# sparrow-smd-jack.net
KiCad netlist of a schematic drawn in EAGLE
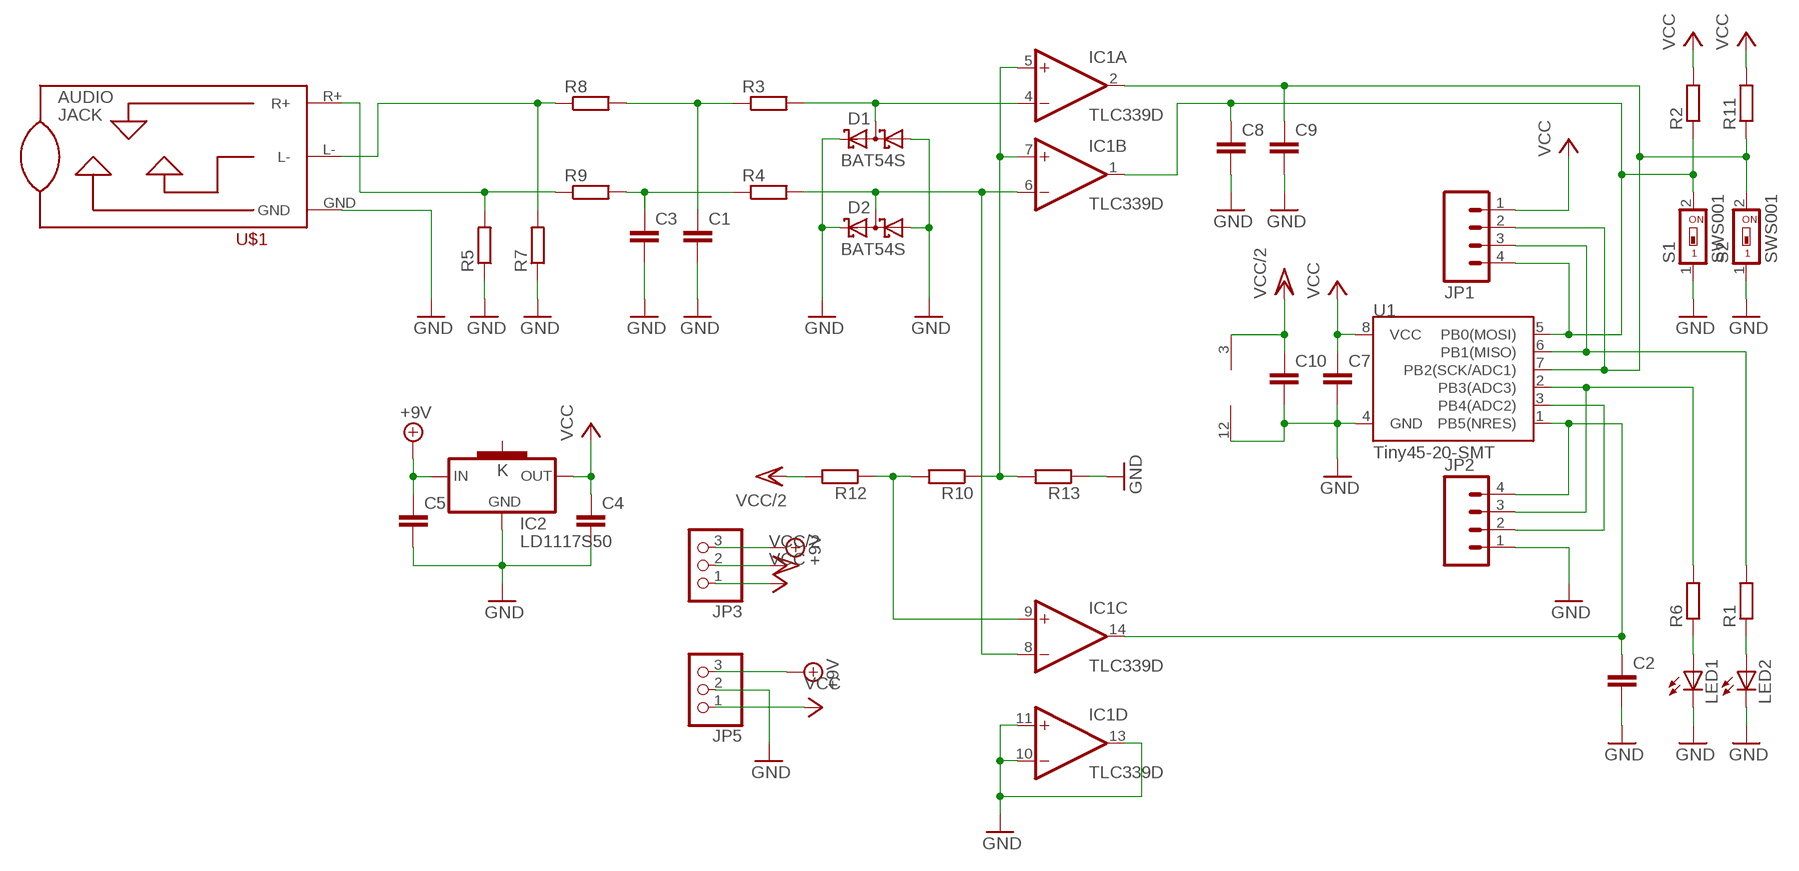
[diagram p0: schematic, sheet 1]

(export (version "E")
  (design (tool "Eeschema 10.0.6"))
  (components
    (comp (ref "C1")
      (value "C-EUC0805K")
      (footprint "eagle-import:C0805K")
      (libsource (lib "eagle-import") (part "C-EUC0805K"))
    )
    (comp (ref "C2")
      (value "C-EUC0805K")
      (footprint "eagle-import:C0805K")
      (libsource (lib "eagle-import") (part "C-EUC0805K"))
    )
    (comp (ref "C3")
      (value "C-EUC0805K")
      (footprint "eagle-import:C0805K")
      (libsource (lib "eagle-import") (part "C-EUC0805K"))
    )
    (comp (ref "C4")
      (value "C-EUC0805K")
      (footprint "eagle-import:C0805K")
      (libsource (lib "eagle-import") (part "C-EUC0805K"))
    )
    (comp (ref "C5")
      (value "C-EUC0805K")
      (footprint "eagle-import:C0805K")
      (libsource (lib "eagle-import") (part "C-EUC0805K"))
    )
    (comp (ref "C7")
      (value "C-EUC0805K")
      (footprint "eagle-import:C0805K")
      (libsource (lib "eagle-import") (part "C-EUC0805K"))
    )
    (comp (ref "C8")
      (value "C-EUC0805K")
      (footprint "eagle-import:C0805K")
      (libsource (lib "eagle-import") (part "C-EUC0805K"))
    )
    (comp (ref "C9")
      (value "C-EUC0805K")
      (footprint "eagle-import:C0805K")
      (libsource (lib "eagle-import") (part "C-EUC0805K"))
    )
    (comp (ref "C10")
      (value "C-EUC0805K")
      (footprint "eagle-import:C0805K")
      (libsource (lib "eagle-import") (part "C-EUC0805K"))
    )
    (comp (ref "D1")
      (value "BAT54S")
      (footprint "eagle-import:SOT23")
      (libsource (lib "eagle-import") (part "BAT54S"))
    )
    (comp (ref "D2")
      (value "BAT54S")
      (footprint "eagle-import:SOT23")
      (libsource (lib "eagle-import") (part "BAT54S"))
    )
    (comp (ref "IC1")
      (value "TLC339D")
      (footprint "eagle-import:SO14")
      (libsource (lib "eagle-import") (part "TLC339D"))
    )
    (comp (ref "IC2")
      (value "LD1117S50")
      (footprint "eagle-import:SOT223")
      (libsource (lib "eagle-import") (part "LD1117S50"))
    )
    (comp (ref "JP1")
      (value "M04PTH")
      (footprint "eagle-import:1X04")
      (libsource (lib "eagle-import") (part "M04PTH"))
    )
    (comp (ref "JP2")
      (value "M04PTH")
      (footprint "eagle-import:1X04")
      (libsource (lib "eagle-import") (part "M04PTH"))
    )
    (comp (ref "JP3")
      (value "PINHD-1X3")
      (footprint "eagle-import:1X03")
      (libsource (lib "eagle-import") (part "PINHD-1X3"))
    )
    (comp (ref "JP5")
      (value "PINHD-1X3")
      (footprint "eagle-import:1X03")
      (libsource (lib "eagle-import") (part "PINHD-1X3"))
    )
    (comp (ref "LED1")
      (value "LEDCHIP-LED0805")
      (footprint "eagle-import:CHIP-LED0805")
      (libsource (lib "eagle-import") (part "LEDCHIP-LED0805"))
    )
    (comp (ref "LED2")
      (value "LEDCHIP-LED0805")
      (footprint "eagle-import:CHIP-LED0805")
      (libsource (lib "eagle-import") (part "LEDCHIP-LED0805"))
    )
    (comp (ref "R1")
      (value "R-EU_M0805")
      (footprint "eagle-import:M0805")
      (libsource (lib "eagle-import") (part "R-EU_M0805"))
    )
    (comp (ref "R2")
      (value "R-EU_M0805")
      (footprint "eagle-import:M0805")
      (libsource (lib "eagle-import") (part "R-EU_M0805"))
    )
    (comp (ref "R3")
      (value "R-EU_M0805")
      (footprint "eagle-import:M0805")
      (libsource (lib "eagle-import") (part "R-EU_M0805"))
    )
    (comp (ref "R4")
      (value "R-EU_M0805")
      (footprint "eagle-import:M0805")
      (libsource (lib "eagle-import") (part "R-EU_M0805"))
    )
    (comp (ref "R5")
      (value "R-EU_M0805")
      (footprint "eagle-import:M0805")
      (libsource (lib "eagle-import") (part "R-EU_M0805"))
    )
    (comp (ref "R6")
      (value "R-EU_M0805")
      (footprint "eagle-import:M0805")
      (libsource (lib "eagle-import") (part "R-EU_M0805"))
    )
    (comp (ref "R7")
      (value "R-EU_M0805")
      (footprint "eagle-import:M0805")
      (libsource (lib "eagle-import") (part "R-EU_M0805"))
    )
    (comp (ref "R8")
      (value "R-EU_M0805")
      (footprint "eagle-import:M0805")
      (libsource (lib "eagle-import") (part "R-EU_M0805"))
    )
    (comp (ref "R9")
      (value "R-EU_M0805")
      (footprint "eagle-import:M0805")
      (libsource (lib "eagle-import") (part "R-EU_M0805"))
    )
    (comp (ref "R10")
      (value "R-EU_M0805")
      (footprint "eagle-import:M0805")
      (libsource (lib "eagle-import") (part "R-EU_M0805"))
    )
    (comp (ref "R11")
      (value "R-EU_M0805")
      (footprint "eagle-import:M0805")
      (libsource (lib "eagle-import") (part "R-EU_M0805"))
    )
    (comp (ref "R12")
      (value "R-EU_M0805")
      (footprint "eagle-import:M0805")
      (libsource (lib "eagle-import") (part "R-EU_M0805"))
    )
    (comp (ref "R13")
      (value "R-EU_M0805")
      (footprint "eagle-import:M0805")
      (libsource (lib "eagle-import") (part "R-EU_M0805"))
    )
    (comp (ref "S1")
      (value "SWS001")
      (footprint "eagle-import:SMS-001")
      (libsource (lib "eagle-import") (part "SWS001"))
    )
    (comp (ref "S2")
      (value "SWS001")
      (footprint "eagle-import:SMS-001")
      (libsource (lib "eagle-import") (part "SWS001"))
    )
    (comp (ref "U$1")
      (value "AUDIO-JACK-SMDSMD")
      (footprint "eagle-import:AUDIO-JACK-SMD")
      (libsource (lib "eagle-import") (part "AUDIO-JACK-SMDSMD"))
    )
    (comp (ref "U1")
      (value "Tiny45-20-SMT")
      (footprint "eagle-import:SO08-EIAJ")
      (libsource (lib "eagle-import") (part "ATTINY45TINY45-20-SMT"))
    )
  )
  (nets
    (net (code "1") (name "+9V") (class "Default")
      (node (ref "C5") (pin "1") (pinfunction "1_1") (pintype "passive"))
      (node (ref "IC2") (pin "3") (pinfunction "IN_3") (pintype "input"))
      (node (ref "JP3") (pin "3") (pinfunction "3_3") (pintype "passive"))
      (node (ref "JP5") (pin "3") (pinfunction "3_3") (pintype "passive"))
    )
    (net (code "2") (name "GND") (class "Default")
      (node (ref "C1") (pin "2") (pinfunction "2_2") (pintype "passive"))
      (node (ref "C10") (pin "2") (pinfunction "2_2") (pintype "passive"))
      (node (ref "C2") (pin "2") (pinfunction "2_2") (pintype "passive"))
      (node (ref "C3") (pin "2") (pinfunction "2_2") (pintype "passive"))
      (node (ref "C4") (pin "2") (pinfunction "2_2") (pintype "passive"))
      (node (ref "C5") (pin "2") (pinfunction "2_2") (pintype "passive"))
      (node (ref "C7") (pin "2") (pinfunction "2_2") (pintype "passive"))
      (node (ref "C8") (pin "2") (pinfunction "2_2") (pintype "passive"))
      (node (ref "C9") (pin "2") (pinfunction "2_2") (pintype "passive"))
      (node (ref "D1") (pin "1") (pinfunction "A1_1") (pintype "passive"))
      (node (ref "D1") (pin "2") (pinfunction "C2_2") (pintype "passive"))
      (node (ref "D2") (pin "1") (pinfunction "A1_1") (pintype "passive"))
      (node (ref "D2") (pin "2") (pinfunction "C2_2") (pintype "passive"))
      (node (ref "IC1") (pin "10") (pinfunction "-IN_10") (pintype "input"))
      (node (ref "IC1") (pin "11") (pinfunction "+IN_11") (pintype "input"))
      (node (ref "IC1") (pin "12") (pinfunction "V-_12") (pintype "power_in"))
      (node (ref "IC1") (pin "13") (pinfunction "OUT_13") (pintype "output"))
      (node (ref "IC2") (pin "1") (pinfunction "GND_1") (pintype "input"))
      (node (ref "JP2") (pin "1") (pinfunction "1_1") (pintype "passive"))
      (node (ref "JP5") (pin "2") (pinfunction "2_2") (pintype "passive"))
      (node (ref "LED1") (pin "C") (pinfunction "C_C") (pintype "passive"))
      (node (ref "LED2") (pin "C") (pinfunction "C_C") (pintype "passive"))
      (node (ref "R13") (pin "1") (pinfunction "1_1") (pintype "passive"))
      (node (ref "R5") (pin "1") (pinfunction "1_1") (pintype "passive"))
      (node (ref "R7") (pin "1") (pinfunction "1_1") (pintype "passive"))
      (node (ref "S1") (pin "1") (pinfunction "1_1") (pintype "passive"))
      (node (ref "S2") (pin "1") (pinfunction "1_1") (pintype "passive"))
      (node (ref "U$1") (pin "GND") (pinfunction "GND_GND") (pintype "bidirectional"))
      (node (ref "U1") (pin "4") (pinfunction "GND_4") (pintype "bidirectional"))
    )
    (net (code "3") (name "Net-(C1-Pad1)") (class "Default")
      (node (ref "C1") (pin "1") (pinfunction "1_1") (pintype "passive"))
      (node (ref "R3") (pin "1") (pinfunction "1_1") (pintype "passive"))
      (node (ref "R8") (pin "2") (pinfunction "2_2") (pintype "passive"))
    )
    (net (code "4") (name "Net-(C3-Pad1)") (class "Default")
      (node (ref "C3") (pin "1") (pinfunction "1_1") (pintype "passive"))
      (node (ref "R4") (pin "1") (pinfunction "1_1") (pintype "passive"))
      (node (ref "R9") (pin "2") (pinfunction "2_2") (pintype "passive"))
    )
    (net (code "5") (name "Net-(D1-C1A2)") (class "Default")
      (node (ref "D1") (pin "3") (pinfunction "C1A2_3") (pintype "passive"))
      (node (ref "IC1") (pin "4") (pinfunction "-IN_4") (pintype "input"))
      (node (ref "R3") (pin "2") (pinfunction "2_2") (pintype "passive"))
    )
    (net (code "6") (name "Net-(D2-C1A2)") (class "Default")
      (node (ref "D2") (pin "3") (pinfunction "C1A2_3") (pintype "passive"))
      (node (ref "IC1") (pin "6") (pinfunction "-IN_6") (pintype "input"))
      (node (ref "IC1") (pin "8") (pinfunction "-IN_8") (pintype "input"))
      (node (ref "R4") (pin "2") (pinfunction "2_2") (pintype "passive"))
    )
    (net (code "7") (name "Net-(IC1A-+IN)") (class "Default")
      (node (ref "IC1") (pin "5") (pinfunction "+IN_5") (pintype "input"))
      (node (ref "IC1") (pin "7") (pinfunction "+IN_7") (pintype "input"))
      (node (ref "R10") (pin "1") (pinfunction "1_1") (pintype "passive"))
      (node (ref "R13") (pin "2") (pinfunction "2_2") (pintype "passive"))
    )
    (net (code "8") (name "Net-(IC1A-OUT)") (class "Default")
      (node (ref "C9") (pin "1") (pinfunction "1_1") (pintype "passive"))
      (node (ref "IC1") (pin "2") (pinfunction "OUT_2") (pintype "output"))
      (node (ref "JP1") (pin "2") (pinfunction "2_2") (pintype "passive"))
      (node (ref "R11") (pin "1") (pinfunction "1_1") (pintype "passive"))
      (node (ref "S2") (pin "2") (pinfunction "2_2") (pintype "passive"))
      (node (ref "U1") (pin "7") (pinfunction "PB2(SCK/ADC1)_7") (pintype "bidirectional"))
    )
    (net (code "9") (name "Net-(IC1B-OUT)") (class "Default")
      (node (ref "C8") (pin "1") (pinfunction "1_1") (pintype "passive"))
      (node (ref "IC1") (pin "1") (pinfunction "OUT_1") (pintype "output"))
      (node (ref "JP1") (pin "4") (pinfunction "4_4") (pintype "passive"))
      (node (ref "R2") (pin "1") (pinfunction "1_1") (pintype "passive"))
      (node (ref "S1") (pin "2") (pinfunction "2_2") (pintype "passive"))
      (node (ref "U1") (pin "5") (pinfunction "PB0(MOSI)_5") (pintype "bidirectional"))
    )
    (net (code "10") (name "Net-(IC1C-+IN)") (class "Default")
      (node (ref "IC1") (pin "9") (pinfunction "+IN_9") (pintype "input"))
      (node (ref "R10") (pin "2") (pinfunction "2_2") (pintype "passive"))
      (node (ref "R12") (pin "1") (pinfunction "1_1") (pintype "passive"))
    )
    (net (code "11") (name "Net-(IC1C-OUT)") (class "Default")
      (node (ref "C2") (pin "1") (pinfunction "1_1") (pintype "passive"))
      (node (ref "IC1") (pin "14") (pinfunction "OUT_14") (pintype "output"))
      (node (ref "JP2") (pin "4") (pinfunction "4_4") (pintype "passive"))
      (node (ref "U1") (pin "1") (pinfunction "PB5(NRES)_1") (pintype "bidirectional"))
    )
    (net (code "12") (name "Net-(LED1-PadA)") (class "Default")
      (node (ref "LED1") (pin "A") (pinfunction "A_A") (pintype "passive"))
      (node (ref "R6") (pin "1") (pinfunction "1_1") (pintype "passive"))
    )
    (net (code "13") (name "Net-(LED2-PadA)") (class "Default")
      (node (ref "LED2") (pin "A") (pinfunction "A_A") (pintype "passive"))
      (node (ref "R1") (pin "1") (pinfunction "1_1") (pintype "passive"))
    )
    (net (code "14") (name "Net-(R5-Pad2)") (class "Default")
      (node (ref "R5") (pin "2") (pinfunction "2_2") (pintype "passive"))
      (node (ref "R9") (pin "1") (pinfunction "1_1") (pintype "passive"))
      (node (ref "U$1") (pin "R+") (pinfunction "R+_R+") (pintype "bidirectional"))
    )
    (net (code "15") (name "Net-(R7-Pad2)") (class "Default")
      (node (ref "R7") (pin "2") (pinfunction "2_2") (pintype "passive"))
      (node (ref "R8") (pin "1") (pinfunction "1_1") (pintype "passive"))
      (node (ref "U$1") (pin "L-") (pinfunction "L-_L-") (pintype "bidirectional"))
    )
    (net (code "16") (name "Net-(U1-PB1(MISO))") (class "Default")
      (node (ref "JP1") (pin "3") (pinfunction "3_3") (pintype "passive"))
      (node (ref "R1") (pin "2") (pinfunction "2_2") (pintype "passive"))
      (node (ref "U1") (pin "6") (pinfunction "PB1(MISO)_6") (pintype "bidirectional"))
    )
    (net (code "17") (name "Net-(U1-PB3(ADC3))") (class "Default")
      (node (ref "JP2") (pin "3") (pinfunction "3_3") (pintype "passive"))
      (node (ref "R6") (pin "2") (pinfunction "2_2") (pintype "passive"))
      (node (ref "U1") (pin "2") (pinfunction "PB3(ADC3)_2") (pintype "bidirectional"))
    )
    (net (code "18") (name "Net-(U1-PB4(ADC2))") (class "Default")
      (node (ref "JP2") (pin "2") (pinfunction "2_2") (pintype "passive"))
      (node (ref "U1") (pin "3") (pinfunction "PB4(ADC2)_3") (pintype "bidirectional"))
    )
    (net (code "19") (name "VCC") (class "Default")
      (node (ref "C4") (pin "1") (pinfunction "1_1") (pintype "passive"))
      (node (ref "C7") (pin "1") (pinfunction "1_1") (pintype "passive"))
      (node (ref "IC2") (pin "2") (pinfunction "OUT_2") (pintype "passive"))
      (node (ref "JP1") (pin "1") (pinfunction "1_1") (pintype "passive"))
      (node (ref "JP3") (pin "1") (pinfunction "1_1") (pintype "passive"))
      (node (ref "JP5") (pin "1") (pinfunction "1_1") (pintype "passive"))
      (node (ref "R11") (pin "2") (pinfunction "2_2") (pintype "passive"))
      (node (ref "R2") (pin "2") (pinfunction "2_2") (pintype "passive"))
      (node (ref "U1") (pin "8") (pinfunction "VCC_8") (pintype "bidirectional"))
    )
    (net (code "20") (name "VCC{slash}2") (class "Default")
      (node (ref "C10") (pin "1") (pinfunction "1_1") (pintype "passive"))
      (node (ref "IC1") (pin "3") (pinfunction "V+_3") (pintype "power_in"))
      (node (ref "JP3") (pin "2") (pinfunction "2_2") (pintype "passive"))
      (node (ref "R12") (pin "2") (pinfunction "2_2") (pintype "passive"))
    )
    (net (code "21") (name "unconnected-(IC2-K-Pad4)") (class "Default")
      (node (ref "IC2") (pin "4") (pinfunction "K_4") (pintype "passive"))
    )
  )
)
